# EAGLE.net
KiCad netlist of a schematic drawn in EAGLE
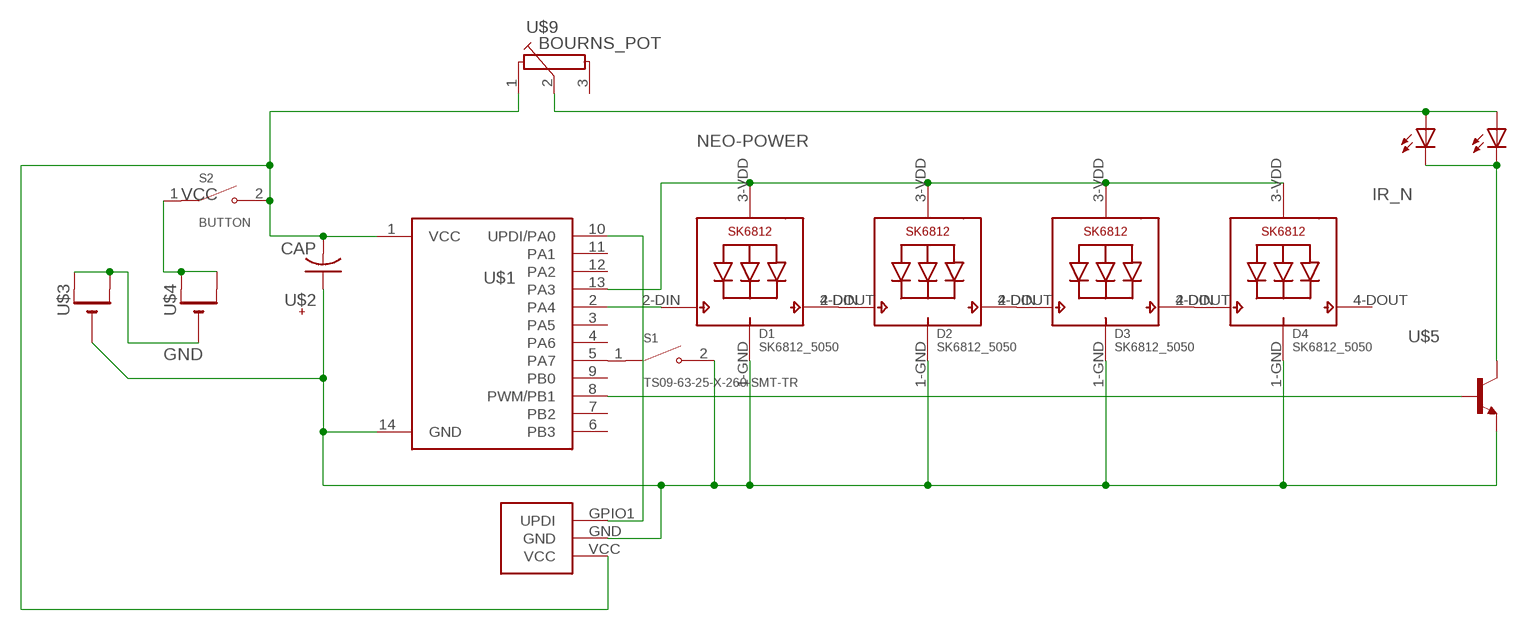
[diagram p0: schematic, sheet 1]

(export (version "E")
  (design (tool "Eeschema 10.0.6"))
  (components
    (comp (ref "D1")
      (value "SK6812_5050")
      (footprint "eagle-import:SK6812_REVERSE_W_CUT")
      (libsource (lib "eagle-import") (part "SK6812_5050"))
    )
    (comp (ref "D2")
      (value "SK6812_5050")
      (footprint "eagle-import:SK6812_REVERSE_W_CUT")
      (libsource (lib "eagle-import") (part "SK6812_5050"))
    )
    (comp (ref "D3")
      (value "SK6812_5050")
      (footprint "eagle-import:SK6812_REVERSE_W_CUT")
      (libsource (lib "eagle-import") (part "SK6812_5050"))
    )
    (comp (ref "D4")
      (value "SK6812_5050")
      (footprint "eagle-import:SK6812_REVERSE_W_CUT")
      (libsource (lib "eagle-import") (part "SK6812_5050"))
    )
    (comp (ref "S1")
      (value "TS09-63-25-X-260-SMT-TR")
      (footprint "eagle-import:SW_TS09-63-25-X-260-SMT-TR")
      (fields (field (name "MANUFACTURER") "CUI Devices"))
      (libsource (lib "eagle-import") (part "TS09-63-25-X-260-SMT-TR"))
    )
    (comp (ref "S2")
      (value "BUTTON")
      (footprint "eagle-import:SW_TS09-63-25-X-260-SMT-TR")
      (fields (field (name "MANUFACTURER") "CUI Devices"))
      (libsource (lib "eagle-import") (part "BUTTON"))
    )
    (comp (ref "U$1")
      (value "ATTINY1614ATTINY1614")
      (footprint "eagle-import:SO14")
      (libsource (lib "eagle-import") (part "ATTINY1614ATTINY1614"))
    )
    (comp (ref "U$2")
      (value "CAP")
      (footprint "eagle-import:UD-6,3X5,8_NICHICON")
      (libsource (lib "eagle-import") (part "CAP"))
    )
    (comp (ref "U$3")
      (value "CR2032SMT")
      (footprint "eagle-import:CR2032-SMD")
      (libsource (lib "eagle-import") (part "CR2032SMT"))
    )
    (comp (ref "U$4")
      (value "CR2032SMT")
      (footprint "eagle-import:CR2032-SMD")
      (libsource (lib "eagle-import") (part "CR2032SMT"))
    )
    (comp (ref "U$5")
      (value "NPN")
      (footprint "eagle-import:SOT23")
      (libsource (lib "eagle-import") (part "NPN"))
    )
    (comp (ref "U$6")
      (value "LEDSIDESOLDER")
      (footprint "eagle-import:LED3MM_5MM_SIDESOLDER")
      (libsource (lib "eagle-import") (part "LEDSIDESOLDER"))
    )
    (comp (ref "U$7")
      (value "LEDSIDESOLDER")
      (footprint "eagle-import:LED3MM_5MM_SIDESOLDER")
      (libsource (lib "eagle-import") (part "LEDSIDESOLDER"))
    )
    (comp (ref "U$8")
      (value "SAO")
      (footprint "eagle-import:SAO_SMD")
      (libsource (lib "eagle-import") (part "SAO"))
    )
    (comp (ref "U$9")
      (value "BOURNS_POT")
      (footprint "eagle-import:3223W")
      (libsource (lib "eagle-import") (part "BOURNS_POT"))
    )
  )
  (nets
    (net (code "1") (name "/GND") (class "Default")
      (node (ref "D1") (pin "1-GND") (pinfunction "GND_1-GND") (pintype "power_in"))
      (node (ref "D2") (pin "1-GND") (pinfunction "GND_1-GND") (pintype "power_in"))
      (node (ref "D3") (pin "1-GND") (pinfunction "GND_1-GND") (pintype "power_in"))
      (node (ref "D4") (pin "1-GND") (pinfunction "GND_1-GND") (pintype "power_in"))
      (node (ref "S1") (pin "2") (pinfunction "2_2") (pintype "passive"))
      (node (ref "U$1") (pin "14") (pinfunction "GND_14") (pintype "power_in"))
      (node (ref "U$2") (pin "+") (pinfunction "+_+") (pintype "bidirectional"))
      (node (ref "U$3") (pin "GND") (pinfunction "GND_GND") (pintype "passive"))
      (node (ref "U$5") (pin "2") (pinfunction "E_2") (pintype "passive"))
      (node (ref "U$8") (pin "GND") (pinfunction "GND_GND") (pintype "bidirectional"))
    )
    (net (code "2") (name "/IR_N") (class "Default")
      (node (ref "U$5") (pin "3") (pinfunction "C_3") (pintype "passive"))
      (node (ref "U$6") (pin "KN") (pinfunction "C_KN") (pintype "passive"))
      (node (ref "U$7") (pin "KN") (pinfunction "C_KN") (pintype "passive"))
    )
    (net (code "3") (name "/NEO-POWER") (class "Default")
      (node (ref "D1") (pin "3-VDD") (pinfunction "VDD_3-VDD") (pintype "power_in"))
      (node (ref "D2") (pin "3-VDD") (pinfunction "VDD_3-VDD") (pintype "power_in"))
      (node (ref "D3") (pin "3-VDD") (pinfunction "VDD_3-VDD") (pintype "power_in"))
      (node (ref "D4") (pin "3-VDD") (pinfunction "VDD_3-VDD") (pintype "power_in"))
      (node (ref "U$1") (pin "13") (pinfunction "PA3_13") (pintype "bidirectional"))
    )
    (net (code "4") (name "/VCC") (class "Default")
      (node (ref "S2") (pin "2") (pinfunction "2_2") (pintype "passive"))
      (node (ref "U$1") (pin "1") (pinfunction "VCC_1") (pintype "power_in"))
      (node (ref "U$2") (pin "-") (pinfunction "-_-") (pintype "bidirectional"))
      (node (ref "U$8") (pin "VCC") (pinfunction "VCC_VCC") (pintype "bidirectional"))
      (node (ref "U$9") (pin "1") (pinfunction "1A_1") (pintype "passive"))
    )
    (net (code "5") (name "Net-(D1-DI)") (class "Default")
      (node (ref "D1") (pin "2-DIN") (pinfunction "DI_2-DIN") (pintype "input"))
      (node (ref "U$1") (pin "2") (pinfunction "PA4_2") (pintype "bidirectional"))
    )
    (net (code "6") (name "Net-(D1-DO)") (class "Default")
      (node (ref "D1") (pin "4-DOUT") (pinfunction "DO_4-DOUT") (pintype "output"))
      (node (ref "D2") (pin "2-DIN") (pinfunction "DI_2-DIN") (pintype "input"))
    )
    (net (code "7") (name "Net-(D2-DO)") (class "Default")
      (node (ref "D2") (pin "4-DOUT") (pinfunction "DO_4-DOUT") (pintype "output"))
      (node (ref "D3") (pin "2-DIN") (pinfunction "DI_2-DIN") (pintype "input"))
    )
    (net (code "8") (name "Net-(D3-DO)") (class "Default")
      (node (ref "D3") (pin "4-DOUT") (pinfunction "DO_4-DOUT") (pintype "output"))
      (node (ref "D4") (pin "2-DIN") (pinfunction "DI_2-DIN") (pintype "input"))
    )
    (net (code "9") (name "Net-(U$1-PA7)") (class "Default")
      (node (ref "S1") (pin "1") (pinfunction "1_1") (pintype "passive"))
      (node (ref "U$1") (pin "5") (pinfunction "PA7_5") (pintype "bidirectional"))
    )
    (net (code "10") (name "Net-(U$1-PWM{slash}PB1)") (class "Default")
      (node (ref "U$1") (pin "8") (pinfunction "PWM/PB1_8") (pintype "bidirectional"))
      (node (ref "U$5") (pin "1") (pinfunction "B_1") (pintype "passive"))
    )
    (net (code "11") (name "Net-(U$1-UPDI{slash}PA0)") (class "Default")
      (node (ref "U$1") (pin "10") (pinfunction "UPDI/PA0_10") (pintype "bidirectional"))
      (node (ref "U$8") (pin "GPIO1") (pinfunction "UPDI_GPIO1") (pintype "bidirectional"))
    )
    (net (code "12") (name "Net-(U$3-+)") (class "Default")
      (node (ref "U$3") (pin "+$1") (pinfunction "+_+$1") (pintype "passive"))
      (node (ref "U$3") (pin "+$2") (pinfunction "+1_+$2") (pintype "passive"))
      (node (ref "U$4") (pin "GND") (pinfunction "GND_GND") (pintype "passive"))
    )
    (net (code "13") (name "Net-(U$4-+)") (class "Default")
      (node (ref "S2") (pin "1") (pinfunction "1_1") (pintype "passive"))
      (node (ref "U$4") (pin "+$1") (pinfunction "+_+$1") (pintype "passive"))
      (node (ref "U$4") (pin "+$2") (pinfunction "+1_+$2") (pintype "passive"))
    )
    (net (code "14") (name "Net-(U$6-A)") (class "Default")
      (node (ref "U$6") (pin "AN") (pinfunction "A_AN") (pintype "passive"))
      (node (ref "U$7") (pin "AN") (pinfunction "A_AN") (pintype "passive"))
      (node (ref "U$9") (pin "2") (pinfunction "1S_2") (pintype "passive"))
    )
    (net (code "15") (name "unconnected-(D4-DO-Pad4-DOUT)") (class "Default")
      (node (ref "D4") (pin "4-DOUT") (pinfunction "DO_4-DOUT") (pintype "output"))
    )
    (net (code "16") (name "unconnected-(U$1-PA1-Pad11)") (class "Default")
      (node (ref "U$1") (pin "11") (pinfunction "PA1_11") (pintype "bidirectional"))
    )
    (net (code "17") (name "unconnected-(U$1-PA2-Pad12)") (class "Default")
      (node (ref "U$1") (pin "12") (pinfunction "PA2_12") (pintype "bidirectional"))
    )
    (net (code "18") (name "unconnected-(U$1-PA5-Pad3)") (class "Default")
      (node (ref "U$1") (pin "3") (pinfunction "PA5_3") (pintype "bidirectional"))
    )
    (net (code "19") (name "unconnected-(U$1-PA6-Pad4)") (class "Default")
      (node (ref "U$1") (pin "4") (pinfunction "PA6_4") (pintype "bidirectional"))
    )
    (net (code "20") (name "unconnected-(U$1-PB0-Pad9)") (class "Default")
      (node (ref "U$1") (pin "9") (pinfunction "PB0_9") (pintype "bidirectional"))
    )
    (net (code "21") (name "unconnected-(U$1-PB2-Pad7)") (class "Default")
      (node (ref "U$1") (pin "7") (pinfunction "PB2_7") (pintype "bidirectional"))
    )
    (net (code "22") (name "unconnected-(U$1-PB3-Pad6)") (class "Default")
      (node (ref "U$1") (pin "6") (pinfunction "PB3_6") (pintype "bidirectional"))
    )
    (net (code "23") (name "unconnected-(U$9-1E-Pad3)") (class "Default")
      (node (ref "U$9") (pin "3") (pinfunction "1E_3") (pintype "passive"))
    )
  )
)
